# 25_UBX_test.net
KiCad netlist of a schematic drawn in EAGLE
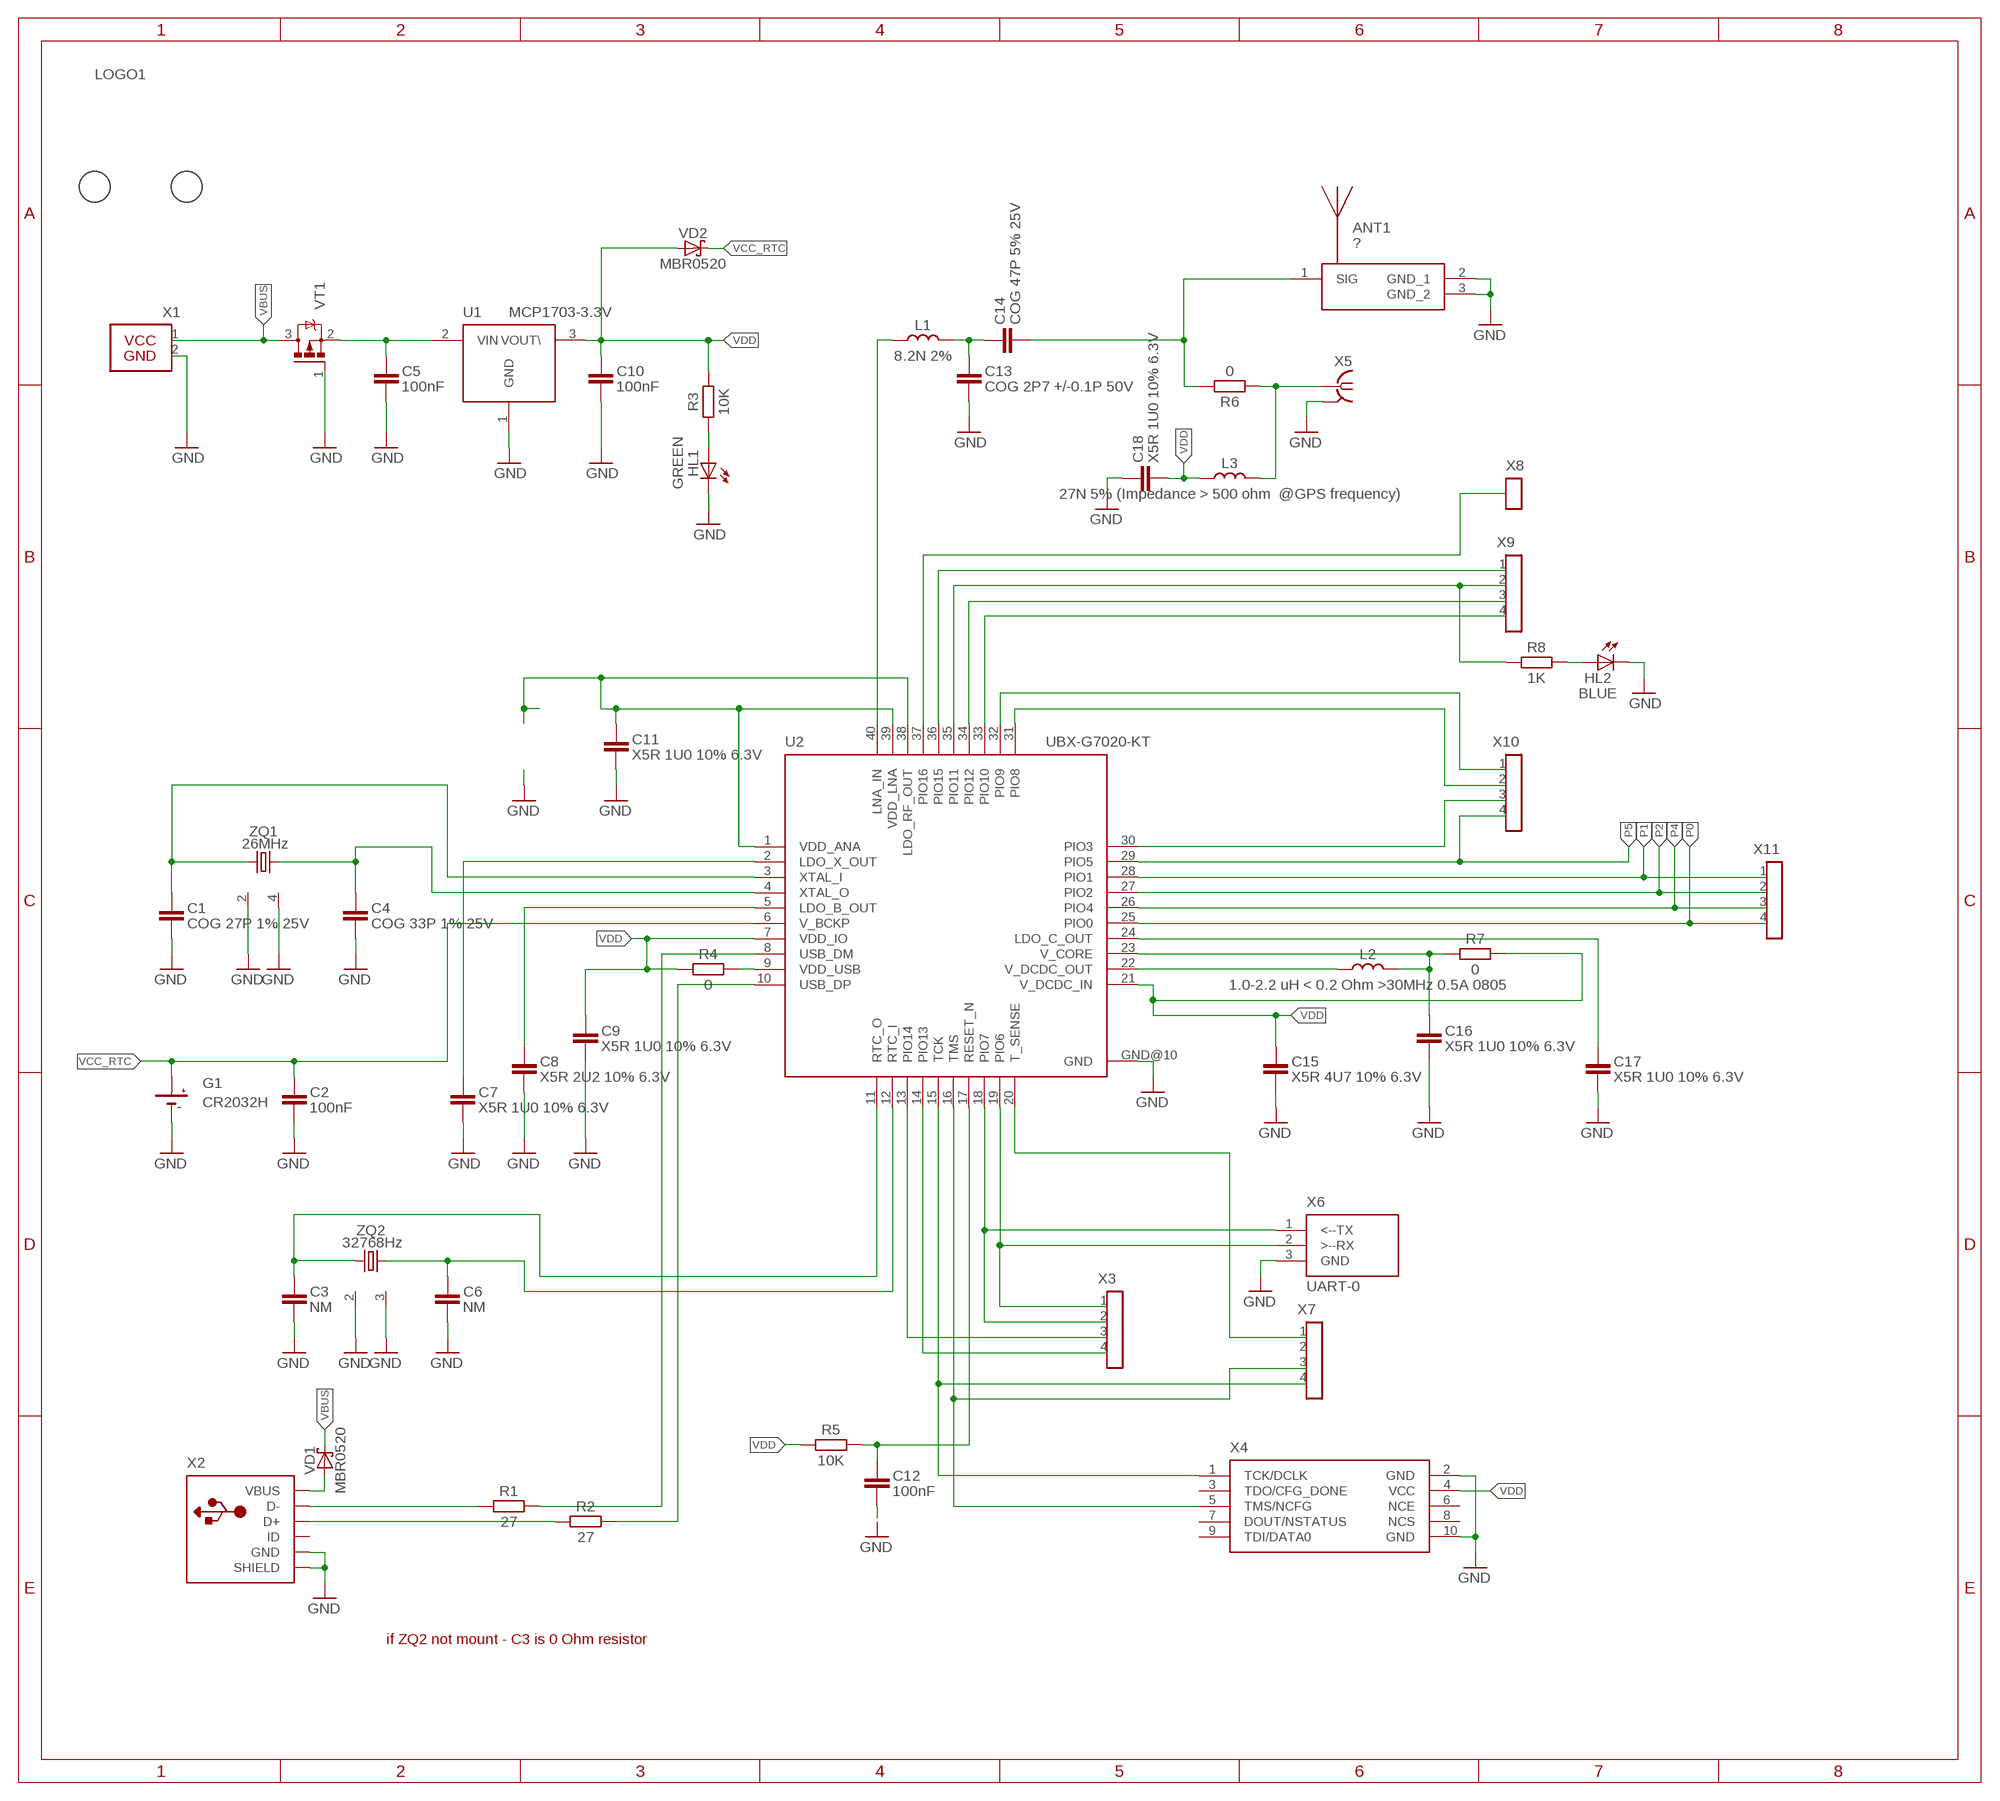
[diagram p0: schematic, sheet 1]

(export (version "E")
  (design (tool "Eeschema 10.0.6"))
  (components
    (comp (ref "ANT1")
      (value "?")
      (footprint "eagle-import:ANTENNA-GPS-AMAN1003030ST01")
      (libsource (lib "eagle-import") (part "ANT-GPS-3"))
    )
    (comp (ref "C1")
      (value "COG 27P 1% 25V")
      (footprint "eagle-import:C0603")
      (libsource (lib "eagle-import") (part "C-EU-C0603"))
    )
    (comp (ref "C2")
      (value "100nF")
      (footprint "eagle-import:C0603")
      (libsource (lib "eagle-import") (part "C-EU-C0603"))
    )
    (comp (ref "C3")
      (value "NM")
      (footprint "eagle-import:C0402")
      (libsource (lib "eagle-import") (part "C-EU-C0402"))
    )
    (comp (ref "C4")
      (value "COG 33P 1% 25V")
      (footprint "eagle-import:C0603")
      (libsource (lib "eagle-import") (part "C-EU-C0603"))
    )
    (comp (ref "C5")
      (value "100nF")
      (footprint "eagle-import:C0805")
      (libsource (lib "eagle-import") (part "C-EU-C0805"))
    )
    (comp (ref "C6")
      (value "NM")
      (footprint "eagle-import:C0402")
      (libsource (lib "eagle-import") (part "C-EU-C0402"))
    )
    (comp (ref "C7")
      (value "X5R 1U0 10% 6.3V")
      (footprint "eagle-import:C0603")
      (libsource (lib "eagle-import") (part "C-EU-C0603"))
    )
    (comp (ref "C8")
      (value "X5R 2U2 10% 6.3V")
      (footprint "eagle-import:C0603")
      (libsource (lib "eagle-import") (part "C-EU-C0603"))
    )
    (comp (ref "C9")
      (value "X5R 1U0 10% 6.3V")
      (footprint "eagle-import:C0603")
      (libsource (lib "eagle-import") (part "C-EU-C0603"))
    )
    (comp (ref "C10")
      (value "100nF")
      (footprint "eagle-import:C1206")
      (libsource (lib "eagle-import") (part "C-EU-C1206"))
    )
    (comp (ref "C11")
      (value "X5R 1U0 10% 6.3V")
      (footprint "eagle-import:C0603")
      (libsource (lib "eagle-import") (part "C-EU-C0603"))
    )
    (comp (ref "C12")
      (value "100nF")
      (footprint "eagle-import:C0603")
      (libsource (lib "eagle-import") (part "C-EU-C0603"))
    )
    (comp (ref "C13")
      (value "COG 2P7 +/-0.1P 50V")
      (footprint "eagle-import:C0603")
      (libsource (lib "eagle-import") (part "C-EU-C0603"))
    )
    (comp (ref "C14")
      (value "COG 47P 5% 25V")
      (footprint "eagle-import:C0603")
      (libsource (lib "eagle-import") (part "C-EU-C0603"))
    )
    (comp (ref "C15")
      (value "X5R 4U7 10% 6.3V")
      (footprint "eagle-import:C0603")
      (libsource (lib "eagle-import") (part "C-EU-C0603"))
    )
    (comp (ref "C16")
      (value "X5R 1U0 10% 6.3V")
      (footprint "eagle-import:C0603")
      (libsource (lib "eagle-import") (part "C-EU-C0603"))
    )
    (comp (ref "C17")
      (value "X5R 1U0 10% 6.3V")
      (footprint "eagle-import:C0603")
      (libsource (lib "eagle-import") (part "C-EU-C0603"))
    )
    (comp (ref "C18")
      (value "X5R 1U0 10% 6.3V")
      (footprint "eagle-import:C0603")
      (libsource (lib "eagle-import") (part "C-EU-C0603"))
    )
    (comp (ref "FIDUCIAL1")
      (value "FIDUCIAL-1MM")
      (footprint "eagle-import:FIDUCIAL_1MM")
      (libsource (lib "eagle-import") (part "FIDUCIAL-1MM"))
    )
    (comp (ref "FIDUCIAL2")
      (value "FIDUCIAL-1MM")
      (footprint "eagle-import:FIDUCIAL_1MM")
      (libsource (lib "eagle-import") (part "FIDUCIAL-1MM"))
    )
    (comp (ref "G1")
      (value "CR2032H")
      (footprint "eagle-import:SN2032")
      (libsource (lib "eagle-import") (part "CR2032H"))
    )
    (comp (ref "HL1")
      (value "GREEN")
      (footprint "eagle-import:CHIPLED_0805")
      (libsource (lib "eagle-import") (part "LED0805"))
    )
    (comp (ref "HL2")
      (value "BLUE")
      (footprint "eagle-import:CHIPLED_0805")
      (libsource (lib "eagle-import") (part "LED0805"))
    )
    (comp (ref "L1")
      (value "8.2N 2%")
      (footprint "eagle-import:L0603-1")
      (libsource (lib "eagle-import") (part "LL0603"))
    )
    (comp (ref "L2")
      (value "1.0-2.2 uH < 0.2 Ohm >30MHz 0.5A 0805")
      (footprint "eagle-import:L0805")
      (libsource (lib "eagle-import") (part "LL0805"))
    )
    (comp (ref "L3")
      (value "27N 5% (Impedance > 500 ohm @GPS frequency)")
      (footprint "eagle-import:L0603-1")
      (libsource (lib "eagle-import") (part "LL0603"))
    )
    (comp (ref "LOGO1")
      (value "LOGO6")
      (footprint "eagle-import:LOGO_OMEGA")
      (libsource (lib "eagle-import") (part "LOGO6"))
    )
    (comp (ref "R1")
      (value "27")
      (footprint "eagle-import:R0603")
      (libsource (lib "eagle-import") (part "R-EU0603"))
    )
    (comp (ref "R2")
      (value "27")
      (footprint "eagle-import:R0603")
      (libsource (lib "eagle-import") (part "R-EU0603"))
    )
    (comp (ref "R3")
      (value "10K")
      (footprint "eagle-import:R0603")
      (libsource (lib "eagle-import") (part "R-EU0603"))
    )
    (comp (ref "R4")
      (value "0")
      (footprint "eagle-import:R0805")
      (libsource (lib "eagle-import") (part "R-EU0805"))
    )
    (comp (ref "R5")
      (value "10K")
      (footprint "eagle-import:R0603")
      (libsource (lib "eagle-import") (part "R-EU0603"))
    )
    (comp (ref "R6")
      (value "0")
      (footprint "eagle-import:R0603")
      (libsource (lib "eagle-import") (part "R-EU0603"))
    )
    (comp (ref "R7")
      (value "0")
      (footprint "eagle-import:R0603")
      (libsource (lib "eagle-import") (part "R-EU0603"))
    )
    (comp (ref "R8")
      (value "1K")
      (footprint "eagle-import:R0603")
      (libsource (lib "eagle-import") (part "R-EU0603"))
    )
    (comp (ref "U1")
      (value "MCP1703-3.3V")
      (footprint "eagle-import:SOT89")
      (libsource (lib "eagle-import") (part "MCP170XSOT89"))
    )
    (comp (ref "U2")
      (value "UBX-G7020-KT")
      (footprint "eagle-import:QFN40-5X5")
      (libsource (lib "eagle-import") (part "UBX-G7020-KT"))
    )
    (comp (ref "VD1")
      (value "MBR0520")
      (footprint "eagle-import:SOD123")
      (libsource (lib "eagle-import") (part "SCHOTTKY-DIODE-SOD123"))
    )
    (comp (ref "VD2")
      (value "MBR0520")
      (footprint "eagle-import:SOD123")
      (libsource (lib "eagle-import") (part "SCHOTTKY-DIODE-SOD123"))
    )
    (comp (ref "VT1")
      (value "FET_P-SOT23")
      (footprint "eagle-import:SOT23-3-1")
      (libsource (lib "eagle-import") (part "FET_P-SOT23"))
    )
    (comp (ref "X1")
      (value "CON-2P-1")
      (footprint "eagle-import:PLS-2.54-2")
      (libsource (lib "eagle-import") (part "CON-2P-1"))
    )
    (comp (ref "X2")
      (value "USB-5S-MINI")
      (footprint "eagle-import:USB-MINIB-1")
      (libsource (lib "eagle-import") (part "USB-5S-MINI"))
    )
    (comp (ref "X3")
      (value "CON-4PPLS2-4")
      (footprint "eagle-import:PLS2-4")
      (libsource (lib "eagle-import") (part "CON-4PPLS2-4"))
    )
    (comp (ref "X4")
      (value "JTAG-ALTERA-5X2PINHEAD")
      (footprint "eagle-import:ML10_NEW")
      (libsource (lib "eagle-import") (part "JTAG-ALTERA-5X2PINHEAD"))
    )
    (comp (ref "X5")
      (value "U.FL-2")
      (footprint "eagle-import:U.FL.-4PIN")
      (libsource (lib "eagle-import") (part "U.FL-2"))
    )
    (comp (ref "X6")
      (value "UART-0")
      (footprint "eagle-import:PLS-2.54-3")
      (libsource (lib "eagle-import") (part "UART-0"))
    )
    (comp (ref "X7")
      (value "CON-4PPLS2-4")
      (footprint "eagle-import:PLS2-4")
      (libsource (lib "eagle-import") (part "CON-4PPLS2-4"))
    )
    (comp (ref "X8")
      (value "CON-1PPLS2-1")
      (footprint "eagle-import:PLS2-1")
      (libsource (lib "eagle-import") (part "CON-1PPLS2-1"))
    )
    (comp (ref "X9")
      (value "CON-4PPLS2-4")
      (footprint "eagle-import:PLS2-4")
      (libsource (lib "eagle-import") (part "CON-4PPLS2-4"))
    )
    (comp (ref "X10")
      (value "CON-4PPLS2-4")
      (footprint "eagle-import:PLS2-4")
      (libsource (lib "eagle-import") (part "CON-4PPLS2-4"))
    )
    (comp (ref "X11")
      (value "CON-4PPLS2-4")
      (footprint "eagle-import:PLS2-4")
      (libsource (lib "eagle-import") (part "CON-4PPLS2-4"))
    )
    (comp (ref "ZQ1")
      (value "26MHz")
      (footprint "eagle-import:CRYSTAL-SMD-3225")
      (libsource (lib "eagle-import") (part "REZONATOR-4PIN-3225"))
    )
    (comp (ref "ZQ2")
      (value "32768Hz")
      (footprint "eagle-import:SJK-7M")
      (libsource (lib "eagle-import") (part "REZONATOR-4PIN-SJK-7M"))
    )
  )
  (nets
    (net (code "1") (name "GND") (class "Default")
      (node (ref "ANT1") (pin "2") (pinfunction "GND_1_2") (pintype "bidirectional"))
      (node (ref "ANT1") (pin "3") (pinfunction "GND_2_3") (pintype "bidirectional"))
      (node (ref "C1") (pin "2") (pinfunction "2_2") (pintype "passive"))
      (node (ref "C10") (pin "2") (pinfunction "2_2") (pintype "passive"))
      (node (ref "C11") (pin "2") (pinfunction "2_2") (pintype "passive"))
      (node (ref "C12") (pin "2") (pinfunction "2_2") (pintype "passive"))
      (node (ref "C13") (pin "2") (pinfunction "2_2") (pintype "passive"))
      (node (ref "C15") (pin "2") (pinfunction "2_2") (pintype "passive"))
      (node (ref "C16") (pin "2") (pinfunction "2_2") (pintype "passive"))
      (node (ref "C17") (pin "2") (pinfunction "2_2") (pintype "passive"))
      (node (ref "C18") (pin "1") (pinfunction "1_1") (pintype "passive"))
      (node (ref "C2") (pin "2") (pinfunction "2_2") (pintype "passive"))
      (node (ref "C3") (pin "2") (pinfunction "2_2") (pintype "passive"))
      (node (ref "C4") (pin "2") (pinfunction "2_2") (pintype "passive"))
      (node (ref "C5") (pin "2") (pinfunction "2_2") (pintype "passive"))
      (node (ref "C6") (pin "2") (pinfunction "2_2") (pintype "passive"))
      (node (ref "C7") (pin "2") (pinfunction "2_2") (pintype "passive"))
      (node (ref "C8") (pin "2") (pinfunction "2_2") (pintype "passive"))
      (node (ref "C9") (pin "2") (pinfunction "2_2") (pintype "passive"))
      (node (ref "G1") (pin "-BATT") (pinfunction "-_-BATT") (pintype "passive"))
      (node (ref "HL1") (pin "C") (pinfunction "C_C") (pintype "passive"))
      (node (ref "HL2") (pin "C") (pinfunction "C_C") (pintype "passive"))
      (node (ref "U1") (pin "1") (pinfunction "GND_1") (pintype "bidirectional"))
      (node (ref "U2") (pin "GND@10") (pinfunction "GND_GND@10") (pintype "bidirectional"))
      (node (ref "VT1") (pin "1") (pinfunction "G_1") (pintype "passive"))
      (node (ref "X1") (pin "2") (pinfunction "2_2") (pintype "bidirectional"))
      (node (ref "X2") (pin "GND") (pinfunction "GND_GND") (pintype "power_in"))
      (node (ref "X2") (pin "SHIELD@1") (pinfunction "SHIELD_SHIELD@1") (pintype "bidirectional"))
      (node (ref "X2") (pin "SHIELD@2") (pinfunction "SHIELD_SHIELD@2") (pintype "bidirectional"))
      (node (ref "X2") (pin "SHIELD@3") (pinfunction "SHIELD_SHIELD@3") (pintype "bidirectional"))
      (node (ref "X2") (pin "SHIELD@4") (pinfunction "SHIELD_SHIELD@4") (pintype "bidirectional"))
      (node (ref "X4") (pin "10") (pinfunction "GND_10") (pintype "bidirectional"))
      (node (ref "X4") (pin "2") (pinfunction "GND_2") (pintype "bidirectional"))
      (node (ref "X5") (pin "S@1") (pinfunction "GND_S@1") (pintype "passive"))
      (node (ref "X5") (pin "S@2") (pinfunction "GND_S@2") (pintype "passive"))
      (node (ref "X5") (pin "S@3") (pinfunction "GND_S@3") (pintype "passive"))
      (node (ref "X6") (pin "3") (pinfunction "GND_3") (pintype "bidirectional"))
      (node (ref "ZQ1") (pin "2") (pinfunction "S_2") (pintype "bidirectional"))
      (node (ref "ZQ1") (pin "4") (pinfunction "S_4") (pintype "bidirectional"))
      (node (ref "ZQ2") (pin "2") (pinfunction "S_2") (pintype "bidirectional"))
      (node (ref "ZQ2") (pin "3") (pinfunction "S_3") (pintype "bidirectional"))
    )
    (net (code "2") (name "Net-(ANT1-SIG)") (class "Default")
      (node (ref "ANT1") (pin "1") (pinfunction "SIG_1") (pintype "bidirectional"))
      (node (ref "C14") (pin "2") (pinfunction "2_2") (pintype "passive"))
      (node (ref "R6") (pin "1") (pinfunction "1_1") (pintype "passive"))
    )
    (net (code "3") (name "Net-(HL1-PadA)") (class "Default")
      (node (ref "HL1") (pin "A") (pinfunction "A_A") (pintype "passive"))
      (node (ref "R3") (pin "1") (pinfunction "1_1") (pintype "passive"))
    )
    (net (code "4") (name "Net-(HL2-PadA)") (class "Default")
      (node (ref "HL2") (pin "A") (pinfunction "A_A") (pintype "passive"))
      (node (ref "R8") (pin "2") (pinfunction "2_2") (pintype "passive"))
    )
    (net (code "5") (name "Net-(L1-%1)") (class "Default")
      (node (ref "L1") (pin "1") (pinfunction "%1_1") (pintype "bidirectional"))
      (node (ref "U2") (pin "40") (pinfunction "LNA_IN_40") (pintype "bidirectional"))
    )
    (net (code "6") (name "Net-(L1-%2)") (class "Default")
      (node (ref "C13") (pin "1") (pinfunction "1_1") (pintype "passive"))
      (node (ref "C14") (pin "1") (pinfunction "1_1") (pintype "passive"))
      (node (ref "L1") (pin "2") (pinfunction "%2_2") (pintype "bidirectional"))
    )
    (net (code "7") (name "Net-(L2-%1)") (class "Default")
      (node (ref "L2") (pin "1") (pinfunction "%1_1") (pintype "bidirectional"))
      (node (ref "U2") (pin "22") (pinfunction "V_DCDC_OUT_22") (pintype "bidirectional"))
    )
    (net (code "8") (name "Net-(L2-%2)") (class "Default")
      (node (ref "C16") (pin "1") (pinfunction "1_1") (pintype "passive"))
      (node (ref "L2") (pin "2") (pinfunction "%2_2") (pintype "bidirectional"))
      (node (ref "R7") (pin "1") (pinfunction "1_1") (pintype "passive"))
      (node (ref "U2") (pin "23") (pinfunction "V_CORE_23") (pintype "bidirectional"))
    )
    (net (code "9") (name "Net-(L3-%1)") (class "Default")
      (node (ref "L3") (pin "1") (pinfunction "%1_1") (pintype "bidirectional"))
      (node (ref "R6") (pin "2") (pinfunction "2_2") (pintype "passive"))
      (node (ref "X5") (pin "1") (pinfunction "1_1") (pintype "passive"))
    )
    (net (code "10") (name "Net-(R1-Pad2)") (class "Default")
      (node (ref "R1") (pin "2") (pinfunction "2_2") (pintype "passive"))
      (node (ref "X2") (pin "D-") (pinfunction "D-_D-") (pintype "bidirectional"))
    )
    (net (code "11") (name "Net-(R2-Pad2)") (class "Default")
      (node (ref "R2") (pin "2") (pinfunction "2_2") (pintype "passive"))
      (node (ref "X2") (pin "D+") (pinfunction "D+_D+") (pintype "bidirectional"))
    )
    (net (code "12") (name "Net-(U1-VIN)") (class "Default")
      (node (ref "C5") (pin "1") (pinfunction "1_1") (pintype "passive"))
      (node (ref "U1") (pin "2") (pinfunction "VIN_2") (pintype "bidirectional"))
      (node (ref "VT1") (pin "2") (pinfunction "S_2") (pintype "passive"))
    )
    (net (code "13") (name "Net-(U2-LDO_B_OUT)") (class "Default")
      (node (ref "C8") (pin "1") (pinfunction "1_1") (pintype "passive"))
      (node (ref "U2") (pin "5") (pinfunction "LDO_B_OUT_5") (pintype "bidirectional"))
    )
    (net (code "14") (name "Net-(U2-LDO_C_OUT)") (class "Default")
      (node (ref "C17") (pin "1") (pinfunction "1_1") (pintype "passive"))
      (node (ref "U2") (pin "24") (pinfunction "LDO_C_OUT_24") (pintype "bidirectional"))
    )
    (net (code "15") (name "Net-(U2-LDO_RF_OUT)") (class "Default")
      (node (ref "C11") (pin "1") (pinfunction "1_1") (pintype "passive"))
      (node (ref "U2") (pin "1") (pinfunction "VDD_ANA_1") (pintype "bidirectional"))
      (node (ref "U2") (pin "38") (pinfunction "LDO_RF_OUT_38") (pintype "bidirectional"))
      (node (ref "U2") (pin "39") (pinfunction "VDD_LNA_39") (pintype "bidirectional"))
    )
    (net (code "16") (name "Net-(U2-LDO_X_OUT)") (class "Default")
      (node (ref "C7") (pin "1") (pinfunction "1_1") (pintype "passive"))
      (node (ref "U2") (pin "2") (pinfunction "LDO_X_OUT_2") (pintype "bidirectional"))
    )
    (net (code "17") (name "Net-(U2-PIO3)") (class "Default")
      (node (ref "U2") (pin "30") (pinfunction "PIO3_30") (pintype "bidirectional"))
      (node (ref "X10") (pin "3") (pinfunction "3_3") (pintype "bidirectional"))
    )
    (net (code "18") (name "Net-(U2-PIO6)") (class "Default")
      (node (ref "U2") (pin "19") (pinfunction "PIO6_19") (pintype "bidirectional"))
      (node (ref "X3") (pin "1") (pinfunction "1_1") (pintype "bidirectional"))
      (node (ref "X6") (pin "2") (pinfunction ">--RX_2") (pintype "bidirectional"))
    )
    (net (code "19") (name "Net-(U2-PIO7)") (class "Default")
      (node (ref "U2") (pin "18") (pinfunction "PIO7_18") (pintype "bidirectional"))
      (node (ref "X3") (pin "2") (pinfunction "2_2") (pintype "bidirectional"))
      (node (ref "X6") (pin "1") (pinfunction "<--TX_1") (pintype "bidirectional"))
    )
    (net (code "20") (name "Net-(U2-PIO8)") (class "Default")
      (node (ref "U2") (pin "31") (pinfunction "PIO8_31") (pintype "bidirectional"))
      (node (ref "X10") (pin "2") (pinfunction "2_2") (pintype "bidirectional"))
    )
    (net (code "21") (name "Net-(U2-PIO9)") (class "Default")
      (node (ref "U2") (pin "32") (pinfunction "PIO9_32") (pintype "bidirectional"))
      (node (ref "X10") (pin "1") (pinfunction "1_1") (pintype "bidirectional"))
    )
    (net (code "22") (name "Net-(U2-PIO10)") (class "Default")
      (node (ref "U2") (pin "33") (pinfunction "PIO10_33") (pintype "bidirectional"))
      (node (ref "X9") (pin "4") (pinfunction "4_4") (pintype "bidirectional"))
    )
    (net (code "23") (name "Net-(U2-PIO11)") (class "Default")
      (node (ref "R8") (pin "1") (pinfunction "1_1") (pintype "passive"))
      (node (ref "U2") (pin "35") (pinfunction "PIO11_35") (pintype "bidirectional"))
      (node (ref "X9") (pin "2") (pinfunction "2_2") (pintype "bidirectional"))
    )
    (net (code "24") (name "Net-(U2-PIO12)") (class "Default")
      (node (ref "U2") (pin "34") (pinfunction "PIO12_34") (pintype "bidirectional"))
      (node (ref "X9") (pin "3") (pinfunction "3_3") (pintype "bidirectional"))
    )
    (net (code "25") (name "Net-(U2-PIO13)") (class "Default")
      (node (ref "U2") (pin "14") (pinfunction "PIO13_14") (pintype "bidirectional"))
      (node (ref "X3") (pin "4") (pinfunction "4_4") (pintype "bidirectional"))
    )
    (net (code "26") (name "Net-(U2-PIO14)") (class "Default")
      (node (ref "U2") (pin "13") (pinfunction "PIO14_13") (pintype "bidirectional"))
      (node (ref "X3") (pin "3") (pinfunction "3_3") (pintype "bidirectional"))
    )
    (net (code "27") (name "Net-(U2-PIO15)") (class "Default")
      (node (ref "U2") (pin "36") (pinfunction "PIO15_36") (pintype "bidirectional"))
      (node (ref "X9") (pin "1") (pinfunction "1_1") (pintype "bidirectional"))
    )
    (net (code "28") (name "Net-(U2-PIO16)") (class "Default")
      (node (ref "U2") (pin "37") (pinfunction "PIO16_37") (pintype "bidirectional"))
      (node (ref "X8") (pin "1") (pinfunction "1_1") (pintype "bidirectional"))
    )
    (net (code "29") (name "Net-(U2-RESET_N)") (class "Default")
      (node (ref "C12") (pin "1") (pinfunction "1_1") (pintype "passive"))
      (node (ref "R5") (pin "2") (pinfunction "2_2") (pintype "passive"))
      (node (ref "U2") (pin "17") (pinfunction "RESET_N_17") (pintype "bidirectional"))
    )
    (net (code "30") (name "Net-(U2-RTC_I)") (class "Default")
      (node (ref "C6") (pin "1") (pinfunction "1_1") (pintype "passive"))
      (node (ref "U2") (pin "12") (pinfunction "RTC_I_12") (pintype "bidirectional"))
      (node (ref "ZQ2") (pin "4") (pinfunction "2_4") (pintype "passive"))
    )
    (net (code "31") (name "Net-(U2-RTC_O)") (class "Default")
      (node (ref "C3") (pin "1") (pinfunction "1_1") (pintype "passive"))
      (node (ref "U2") (pin "11") (pinfunction "RTC_O_11") (pintype "bidirectional"))
      (node (ref "ZQ2") (pin "1") (pinfunction "1_1") (pintype "passive"))
    )
    (net (code "32") (name "Net-(U2-TCK)") (class "Default")
      (node (ref "U2") (pin "15") (pinfunction "TCK_15") (pintype "bidirectional"))
      (node (ref "X4") (pin "1") (pinfunction "TCK/DCLK_1") (pintype "bidirectional"))
      (node (ref "X7") (pin "4") (pinfunction "4_4") (pintype "bidirectional"))
    )
    (net (code "33") (name "Net-(U2-TMS)") (class "Default")
      (node (ref "U2") (pin "16") (pinfunction "TMS_16") (pintype "bidirectional"))
      (node (ref "X4") (pin "5") (pinfunction "TMS/NCFG_5") (pintype "bidirectional"))
      (node (ref "X7") (pin "3") (pinfunction "3_3") (pintype "bidirectional"))
    )
    (net (code "34") (name "Net-(U2-T_SENSE)") (class "Default")
      (node (ref "U2") (pin "20") (pinfunction "T_SENSE_20") (pintype "bidirectional"))
      (node (ref "X7") (pin "1") (pinfunction "1_1") (pintype "bidirectional"))
    )
    (net (code "35") (name "Net-(U2-USB_DM)") (class "Default")
      (node (ref "R1") (pin "1") (pinfunction "1_1") (pintype "passive"))
      (node (ref "U2") (pin "8") (pinfunction "USB_DM_8") (pintype "bidirectional"))
    )
    (net (code "36") (name "Net-(U2-USB_DP)") (class "Default")
      (node (ref "R2") (pin "1") (pinfunction "1_1") (pintype "passive"))
      (node (ref "U2") (pin "10") (pinfunction "USB_DP_10") (pintype "bidirectional"))
    )
    (net (code "37") (name "Net-(U2-VDD_USB)") (class "Default")
      (node (ref "R4") (pin "1") (pinfunction "1_1") (pintype "passive"))
      (node (ref "U2") (pin "9") (pinfunction "VDD_USB_9") (pintype "bidirectional"))
    )
    (net (code "38") (name "Net-(U2-XTAL_I)") (class "Default")
      (node (ref "C1") (pin "1") (pinfunction "1_1") (pintype "passive"))
      (node (ref "U2") (pin "3") (pinfunction "XTAL_I_3") (pintype "bidirectional"))
      (node (ref "ZQ1") (pin "1") (pinfunction "1_1") (pintype "passive"))
    )
    (net (code "39") (name "Net-(U2-XTAL_O)") (class "Default")
      (node (ref "C4") (pin "1") (pinfunction "1_1") (pintype "passive"))
      (node (ref "U2") (pin "4") (pinfunction "XTAL_O_4") (pintype "bidirectional"))
      (node (ref "ZQ1") (pin "3") (pinfunction "2_3") (pintype "passive"))
    )
    (net (code "40") (name "Net-(VD1-PadA)") (class "Default")
      (node (ref "VD1") (pin "A") (pinfunction "A_A") (pintype "passive"))
      (node (ref "X2") (pin "VBUS") (pinfunction "VBUS_VBUS") (pintype "bidirectional"))
    )
    (net (code "41") (name "P0") (class "Default")
      (node (ref "U2") (pin "25") (pinfunction "PIO0_25") (pintype "bidirectional"))
      (node (ref "X11") (pin "4") (pinfunction "4_4") (pintype "bidirectional"))
    )
    (net (code "42") (name "P1") (class "Default")
      (node (ref "U2") (pin "28") (pinfunction "PIO1_28") (pintype "bidirectional"))
      (node (ref "X11") (pin "1") (pinfunction "1_1") (pintype "bidirectional"))
    )
    (net (code "43") (name "P2") (class "Default")
      (node (ref "U2") (pin "27") (pinfunction "PIO2_27") (pintype "bidirectional"))
      (node (ref "X11") (pin "2") (pinfunction "2_2") (pintype "bidirectional"))
    )
    (net (code "44") (name "P4") (class "Default")
      (node (ref "U2") (pin "26") (pinfunction "PIO4_26") (pintype "bidirectional"))
      (node (ref "X11") (pin "3") (pinfunction "3_3") (pintype "bidirectional"))
    )
    (net (code "45") (name "P5") (class "Default")
      (node (ref "U2") (pin "29") (pinfunction "PIO5_29") (pintype "bidirectional"))
      (node (ref "X10") (pin "4") (pinfunction "4_4") (pintype "bidirectional"))
    )
    (net (code "46") (name "VBUS") (class "Default")
      (node (ref "VD1") (pin "C") (pinfunction "C_C") (pintype "passive"))
      (node (ref "VT1") (pin "3") (pinfunction "D_3") (pintype "passive"))
      (node (ref "X1") (pin "1") (pinfunction "1_1") (pintype "bidirectional"))
    )
    (net (code "47") (name "VCC_RTC") (class "Default")
      (node (ref "C2") (pin "1") (pinfunction "1_1") (pintype "passive"))
      (node (ref "G1") (pin "+BATT") (pinfunction "+_+BATT") (pintype "passive"))
      (node (ref "U2") (pin "6") (pinfunction "V_BCKP_6") (pintype "bidirectional"))
      (node (ref "VD2") (pin "C") (pinfunction "C_C") (pintype "passive"))
    )
    (net (code "48") (name "VDD") (class "Default")
      (node (ref "C10") (pin "1") (pinfunction "1_1") (pintype "passive"))
      (node (ref "C15") (pin "1") (pinfunction "1_1") (pintype "passive"))
      (node (ref "C18") (pin "2") (pinfunction "2_2") (pintype "passive"))
      (node (ref "C9") (pin "1") (pinfunction "1_1") (pintype "passive"))
      (node (ref "L3") (pin "2") (pinfunction "%2_2") (pintype "bidirectional"))
      (node (ref "R3") (pin "2") (pinfunction "2_2") (pintype "passive"))
      (node (ref "R4") (pin "2") (pinfunction "2_2") (pintype "passive"))
      (node (ref "R5") (pin "1") (pinfunction "1_1") (pintype "passive"))
      (node (ref "R7") (pin "2") (pinfunction "2_2") (pintype "passive"))
      (node (ref "U1") (pin "3") (pinfunction "VOUT\\_3") (pintype "bidirectional"))
      (node (ref "U2") (pin "21") (pinfunction "V_DCDC_IN_21") (pintype "bidirectional"))
      (node (ref "U2") (pin "7") (pinfunction "VDD_IO_7") (pintype "bidirectional"))
      (node (ref "VD2") (pin "A") (pinfunction "A_A") (pintype "passive"))
      (node (ref "X4") (pin "4") (pinfunction "VCC_4") (pintype "bidirectional"))
    )
    (net (code "49") (name "unconnected-(X2-PadID)") (class "Default")
      (node (ref "X2") (pin "ID") (pinfunction "ID_ID") (pintype "bidirectional"))
    )
    (net (code "50") (name "unconnected-(X4-DOUT{slash}NSTATUS-Pad7)") (class "Default")
      (node (ref "X4") (pin "7") (pinfunction "DOUT/NSTATUS_7") (pintype "bidirectional"))
    )
    (net (code "51") (name "unconnected-(X4-NCE-Pad6)") (class "Default")
      (node (ref "X4") (pin "6") (pinfunction "NCE_6") (pintype "bidirectional"))
    )
    (net (code "52") (name "unconnected-(X4-NCS-Pad8)") (class "Default")
      (node (ref "X4") (pin "8") (pinfunction "NCS_8") (pintype "bidirectional"))
    )
    (net (code "53") (name "unconnected-(X4-TDI{slash}DATA0-Pad9)") (class "Default")
      (node (ref "X4") (pin "9") (pinfunction "TDI/DATA0_9") (pintype "bidirectional"))
    )
    (net (code "54") (name "unconnected-(X4-TDO{slash}CFG_DONE-Pad3)") (class "Default")
      (node (ref "X4") (pin "3") (pinfunction "TDO/CFG_DONE_3") (pintype "bidirectional"))
    )
    (net (code "55") (name "unconnected-(X7-Pad2)") (class "Default")
      (node (ref "X7") (pin "2") (pinfunction "2_2") (pintype "bidirectional"))
    )
  )
)
